# AccBottom.net
KiCad netlist of a schematic drawn in Altium Designer
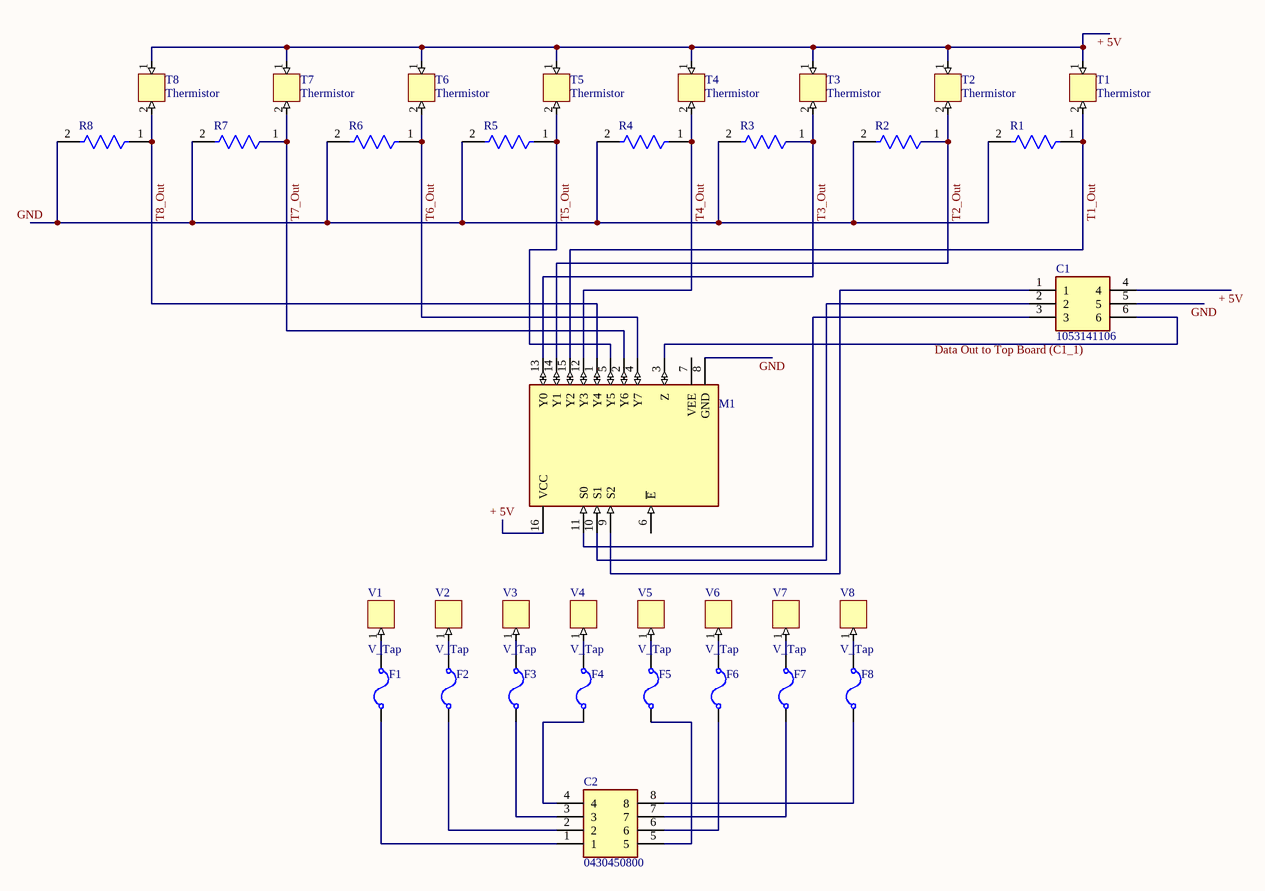
[diagram p0: AccBottom.SchDoc]

(export (version "E")
  (design (tool "Eeschema 10.0.6"))
  (components
    (comp (ref "C1")
      (value "1053141106")
      (footprint "6 Pin Dual Nano")
      (libsource (lib "AccBottom") (part "1053141106"))
    )
    (comp (ref "C2")
      (value "0430450800")
      (footprint "8 Pin Dual")
      (description "Micro-Fit (3.0) dual row, right angle, thru hole header")
      (libsource (lib "AccBottom") (part "0430450800"))
    )
    (comp (ref "F1")
      (value "0ACG-1000-TE")
      (footprint "Fuse")
      (description "Electric Fuse, 1A, 350VAC, 500VDC, 100A (IR), Surface Mount")
      (fields (field (name "MANUFACTURER") "Bel"))
      (libsource (lib "AccBottom") (part "0ACG-1000-TE"))
    )
    (comp (ref "F2")
      (value "0ACG-1000-TE")
      (footprint "Fuse")
      (description "Electric Fuse, 1A, 350VAC, 500VDC, 100A (IR), Surface Mount")
      (fields (field (name "MANUFACTURER") "Bel"))
      (libsource (lib "AccBottom") (part "0ACG-1000-TE"))
    )
    (comp (ref "F3")
      (value "0ACG-1000-TE")
      (footprint "Fuse")
      (description "Electric Fuse, 1A, 350VAC, 500VDC, 100A (IR), Surface Mount")
      (fields (field (name "MANUFACTURER") "Bel"))
      (libsource (lib "AccBottom") (part "0ACG-1000-TE"))
    )
    (comp (ref "F4")
      (value "0ACG-1000-TE")
      (footprint "Fuse")
      (description "Electric Fuse, 1A, 350VAC, 500VDC, 100A (IR), Surface Mount")
      (fields (field (name "MANUFACTURER") "Bel"))
      (libsource (lib "AccBottom") (part "0ACG-1000-TE"))
    )
    (comp (ref "F5")
      (value "0ACG-1000-TE")
      (footprint "Fuse")
      (description "Electric Fuse, 1A, 350VAC, 500VDC, 100A (IR), Surface Mount")
      (fields (field (name "MANUFACTURER") "Bel"))
      (libsource (lib "AccBottom") (part "0ACG-1000-TE"))
    )
    (comp (ref "F6")
      (value "0ACG-1000-TE")
      (footprint "Fuse")
      (description "Electric Fuse, 1A, 350VAC, 500VDC, 100A (IR), Surface Mount")
      (fields (field (name "MANUFACTURER") "Bel"))
      (libsource (lib "AccBottom") (part "0ACG-1000-TE"))
    )
    (comp (ref "F7")
      (value "0ACG-1000-TE")
      (footprint "Fuse")
      (description "Electric Fuse, 1A, 350VAC, 500VDC, 100A (IR), Surface Mount")
      (fields (field (name "MANUFACTURER") "Bel"))
      (libsource (lib "AccBottom") (part "0ACG-1000-TE"))
    )
    (comp (ref "F8")
      (value "0ACG-1000-TE")
      (footprint "Fuse")
      (description "Electric Fuse, 1A, 350VAC, 500VDC, 100A (IR), Surface Mount")
      (fields (field (name "MANUFACTURER") "Bel"))
      (libsource (lib "AccBottom") (part "0ACG-1000-TE"))
    )
    (comp (ref "M1")
      (value "74HC4051D,653")
      (footprint "8x1MUX")
      (description "IC MUX/DEMUX 8X1 16SOIC")
      (libsource (lib "AccBottom") (part "74HC4051D"))
    )
    (comp (ref "R1")
      (value "RC0805FR-133K3L")
      (footprint "3.3kRes")
      (fields
        (field (name "TOLERANCE") "1%")
        (field (name "MANUFACTURER") "KOA Speer")
        (field (name "MANUFACTURER PART NUMBER") "RK73G2ATTD3301F")
      )
      (libsource (lib "AccBottom") (part "RC0805FR-133K3L"))
    )
    (comp (ref "R2")
      (value "RC0805FR-133K3L")
      (footprint "3.3kRes")
      (fields
        (field (name "TOLERANCE") "1%")
        (field (name "MANUFACTURER") "KOA Speer")
        (field (name "MANUFACTURER PART NUMBER") "RK73G2ATTD3301F")
      )
      (libsource (lib "AccBottom") (part "RC0805FR-133K3L"))
    )
    (comp (ref "R3")
      (value "RC0805FR-133K3L")
      (footprint "3.3kRes")
      (fields
        (field (name "TOLERANCE") "1%")
        (field (name "MANUFACTURER") "KOA Speer")
        (field (name "MANUFACTURER PART NUMBER") "RK73G2ATTD3301F")
      )
      (libsource (lib "AccBottom") (part "RC0805FR-133K3L"))
    )
    (comp (ref "R4")
      (value "RC0805FR-133K3L")
      (footprint "3.3kRes")
      (fields
        (field (name "TOLERANCE") "1%")
        (field (name "MANUFACTURER") "KOA Speer")
        (field (name "MANUFACTURER PART NUMBER") "RK73G2ATTD3301F")
      )
      (libsource (lib "AccBottom") (part "RC0805FR-133K3L"))
    )
    (comp (ref "R5")
      (value "RC0805FR-133K3L")
      (footprint "3.3kRes")
      (fields
        (field (name "TOLERANCE") "1%")
        (field (name "MANUFACTURER") "KOA Speer")
        (field (name "MANUFACTURER PART NUMBER") "RK73G2ATTD3301F")
      )
      (libsource (lib "AccBottom") (part "RC0805FR-133K3L"))
    )
    (comp (ref "R6")
      (value "RC0805FR-133K3L")
      (footprint "3.3kRes")
      (fields
        (field (name "TOLERANCE") "1%")
        (field (name "MANUFACTURER") "KOA Speer")
        (field (name "MANUFACTURER PART NUMBER") "RK73G2ATTD3301F")
      )
      (libsource (lib "AccBottom") (part "RC0805FR-133K3L"))
    )
    (comp (ref "R7")
      (value "RC0805FR-133K3L")
      (footprint "3.3kRes")
      (fields
        (field (name "TOLERANCE") "1%")
        (field (name "MANUFACTURER") "KOA Speer")
        (field (name "MANUFACTURER PART NUMBER") "RK73G2ATTD3301F")
      )
      (libsource (lib "AccBottom") (part "RC0805FR-133K3L"))
    )
    (comp (ref "R8")
      (value "RC0805FR-133K3L")
      (footprint "3.3kRes")
      (fields
        (field (name "TOLERANCE") "1%")
        (field (name "MANUFACTURER") "KOA Speer")
        (field (name "MANUFACTURER PART NUMBER") "RK73G2ATTD3301F")
      )
      (libsource (lib "AccBottom") (part "RC0805FR-133K3L"))
    )
    (comp (ref "T1")
      (value "Thermistor")
      (footprint "Thermistor")
      (libsource (lib "AccBottom") (part "Thermistor"))
    )
    (comp (ref "T2")
      (value "Thermistor")
      (footprint "Thermistor")
      (libsource (lib "AccBottom") (part "Thermistor"))
    )
    (comp (ref "T3")
      (value "Thermistor")
      (footprint "Thermistor")
      (libsource (lib "AccBottom") (part "Thermistor"))
    )
    (comp (ref "T4")
      (value "Thermistor")
      (footprint "Thermistor")
      (libsource (lib "AccBottom") (part "Thermistor"))
    )
    (comp (ref "T5")
      (value "Thermistor")
      (footprint "Thermistor")
      (libsource (lib "AccBottom") (part "Thermistor"))
    )
    (comp (ref "T6")
      (value "Thermistor")
      (footprint "Thermistor")
      (libsource (lib "AccBottom") (part "Thermistor"))
    )
    (comp (ref "T7")
      (value "Thermistor")
      (footprint "Thermistor")
      (libsource (lib "AccBottom") (part "Thermistor"))
    )
    (comp (ref "T8")
      (value "Thermistor")
      (footprint "Thermistor")
      (libsource (lib "AccBottom") (part "Thermistor"))
    )
    (comp (ref "V1") (value "V_Tap") (footprint "Voltage tap") (libsource (lib "AccBottom") (part "V_Tap")))
    (comp (ref "V2") (value "V_Tap") (footprint "Voltage tap") (libsource (lib "AccBottom") (part "V_Tap")))
    (comp (ref "V3") (value "V_Tap") (footprint "Voltage tap") (libsource (lib "AccBottom") (part "V_Tap")))
    (comp (ref "V4") (value "V_Tap") (footprint "Voltage tap") (libsource (lib "AccBottom") (part "V_Tap")))
    (comp (ref "V5") (value "V_Tap") (footprint "Voltage tap") (libsource (lib "AccBottom") (part "V_Tap")))
    (comp (ref "V6") (value "V_Tap") (footprint "Voltage tap") (libsource (lib "AccBottom") (part "V_Tap")))
    (comp (ref "V7") (value "V_Tap") (footprint "Voltage tap") (libsource (lib "AccBottom") (part "V_Tap")))
    (comp (ref "V8") (value "V_Tap") (footprint "Voltage tap") (libsource (lib "AccBottom") (part "V_Tap")))
  )
  (nets
    (net (code "1") (name "/+ 5V") (class "Default")
      (node (ref "C1") (pin "4") (pinfunction "4_4") (pintype "passive"))
      (node (ref "M1") (pin "16") (pinfunction "VCC_16") (pintype "power_in"))
      (node (ref "T1") (pin "1") (pintype "input"))
      (node (ref "T2") (pin "1") (pintype "input"))
      (node (ref "T3") (pin "1") (pintype "input"))
      (node (ref "T4") (pin "1") (pintype "input"))
      (node (ref "T5") (pin "1") (pintype "input"))
      (node (ref "T6") (pin "1") (pintype "input"))
      (node (ref "T7") (pin "1") (pintype "input"))
      (node (ref "T8") (pin "1") (pintype "input"))
    )
    (net (code "3") (name "/GND") (class "Default")
      (node (ref "C1") (pin "5") (pinfunction "5_5") (pintype "passive"))
      (node (ref "M1") (pin "8") (pinfunction "GND_8") (pintype "power_in"))
      (node (ref "R1") (pin "2") (pinfunction "2_2") (pintype "passive"))
      (node (ref "R2") (pin "2") (pinfunction "2_2") (pintype "passive"))
      (node (ref "R3") (pin "2") (pinfunction "2_2") (pintype "passive"))
      (node (ref "R4") (pin "2") (pinfunction "2_2") (pintype "passive"))
      (node (ref "R5") (pin "2") (pinfunction "2_2") (pintype "passive"))
      (node (ref "R6") (pin "2") (pinfunction "2_2") (pintype "passive"))
      (node (ref "R7") (pin "2") (pinfunction "2_2") (pintype "passive"))
      (node (ref "R8") (pin "2") (pinfunction "2_2") (pintype "passive"))
    )
    (net (code "4") (name "/T1_Out") (class "Default")
      (node (ref "M1") (pin "15") (pinfunction "Y2_15") (pintype "bidirectional"))
      (node (ref "R1") (pin "1") (pinfunction "1_1") (pintype "passive"))
      (node (ref "T1") (pin "2") (pintype "input"))
    )
    (net (code "5") (name "/T2_Out") (class "Default")
      (node (ref "M1") (pin "14") (pinfunction "Y1_14") (pintype "bidirectional"))
      (node (ref "R2") (pin "1") (pinfunction "1_1") (pintype "passive"))
      (node (ref "T2") (pin "2") (pintype "input"))
    )
    (net (code "6") (name "/T3_Out") (class "Default")
      (node (ref "M1") (pin "13") (pinfunction "Y0_13") (pintype "bidirectional"))
      (node (ref "R3") (pin "1") (pinfunction "1_1") (pintype "passive"))
      (node (ref "T3") (pin "2") (pintype "input"))
    )
    (net (code "7") (name "/T4_Out") (class "Default")
      (node (ref "M1") (pin "12") (pinfunction "Y3_12") (pintype "bidirectional"))
      (node (ref "R4") (pin "1") (pinfunction "1_1") (pintype "passive"))
      (node (ref "T4") (pin "2") (pintype "input"))
    )
    (net (code "8") (name "/T5_Out") (class "Default")
      (node (ref "M1") (pin "5") (pinfunction "Y5_5") (pintype "bidirectional"))
      (node (ref "R5") (pin "1") (pinfunction "1_1") (pintype "passive"))
      (node (ref "T5") (pin "2") (pintype "input"))
    )
    (net (code "9") (name "/T6_Out") (class "Default")
      (node (ref "M1") (pin "4") (pinfunction "Y7_4") (pintype "bidirectional"))
      (node (ref "R6") (pin "1") (pinfunction "1_1") (pintype "passive"))
      (node (ref "T6") (pin "2") (pintype "input"))
    )
    (net (code "10") (name "/T7_Out") (class "Default")
      (node (ref "M1") (pin "2") (pinfunction "Y6_2") (pintype "bidirectional"))
      (node (ref "R7") (pin "1") (pinfunction "1_1") (pintype "passive"))
      (node (ref "T7") (pin "2") (pintype "input"))
    )
    (net (code "11") (name "/T8_Out") (class "Default")
      (node (ref "M1") (pin "1") (pinfunction "Y4_1") (pintype "bidirectional"))
      (node (ref "R8") (pin "1") (pinfunction "1_1") (pintype "passive"))
      (node (ref "T8") (pin "2") (pintype "input"))
    )
    (net (code "12") (name "Net-(C2-Pad1)") (class "Default")
      (node (ref "C2") (pin "1") (pinfunction "1_1") (pintype "passive"))
      (node (ref "F1") (pin "1") (pinfunction "PB6_1") (pintype "passive"))
    )
    (net (code "13") (name "Net-(C2-Pad2)") (class "Default")
      (node (ref "C2") (pin "2") (pinfunction "2_2") (pintype "passive"))
      (node (ref "F2") (pin "1") (pinfunction "PB6_1") (pintype "passive"))
    )
    (net (code "14") (name "Net-(C2-Pad3)") (class "Default")
      (node (ref "C2") (pin "3") (pinfunction "3_3") (pintype "passive"))
      (node (ref "F3") (pin "1") (pinfunction "PB6_1") (pintype "passive"))
    )
    (net (code "15") (name "Net-(C2-Pad4)") (class "Default")
      (node (ref "C2") (pin "4") (pinfunction "4_4") (pintype "passive"))
      (node (ref "F4") (pin "1") (pinfunction "PB6_1") (pintype "passive"))
    )
    (net (code "16") (name "Net-(C2-Pad5)") (class "Default")
      (node (ref "C2") (pin "5") (pinfunction "5_5") (pintype "passive"))
      (node (ref "F5") (pin "1") (pinfunction "PB6_1") (pintype "passive"))
    )
    (net (code "17") (name "Net-(C2-Pad6)") (class "Default")
      (node (ref "C2") (pin "6") (pinfunction "6_6") (pintype "passive"))
      (node (ref "F6") (pin "1") (pinfunction "PB6_1") (pintype "passive"))
    )
    (net (code "18") (name "Net-(C2-Pad7)") (class "Default")
      (node (ref "C2") (pin "7") (pinfunction "7_7") (pintype "passive"))
      (node (ref "F7") (pin "1") (pinfunction "PB6_1") (pintype "passive"))
    )
    (net (code "19") (name "Net-(C2-Pad8)") (class "Default")
      (node (ref "C2") (pin "8") (pinfunction "8_8") (pintype "passive"))
      (node (ref "F8") (pin "1") (pinfunction "PB6_1") (pintype "passive"))
    )
    (net (code "20") (name "Net-(F1-PB6-Pad2)") (class "Default")
      (node (ref "F1") (pin "2") (pinfunction "PB6_2") (pintype "passive"))
      (node (ref "V1") (pin "1") (pintype "input"))
    )
    (net (code "21") (name "Net-(F2-PB6-Pad2)") (class "Default")
      (node (ref "F2") (pin "2") (pinfunction "PB6_2") (pintype "passive"))
      (node (ref "V2") (pin "1") (pintype "input"))
    )
    (net (code "22") (name "Net-(F3-PB6-Pad2)") (class "Default")
      (node (ref "F3") (pin "2") (pinfunction "PB6_2") (pintype "passive"))
      (node (ref "V3") (pin "1") (pintype "input"))
    )
    (net (code "23") (name "Net-(F4-PB6-Pad2)") (class "Default")
      (node (ref "F4") (pin "2") (pinfunction "PB6_2") (pintype "passive"))
      (node (ref "V4") (pin "1") (pintype "input"))
    )
    (net (code "24") (name "Net-(F5-PB6-Pad2)") (class "Default")
      (node (ref "F5") (pin "2") (pinfunction "PB6_2") (pintype "passive"))
      (node (ref "V5") (pin "1") (pintype "input"))
    )
    (net (code "25") (name "Net-(F6-PB6-Pad2)") (class "Default")
      (node (ref "F6") (pin "2") (pinfunction "PB6_2") (pintype "passive"))
      (node (ref "V6") (pin "1") (pintype "input"))
    )
    (net (code "26") (name "Net-(F7-PB6-Pad2)") (class "Default")
      (node (ref "F7") (pin "2") (pinfunction "PB6_2") (pintype "passive"))
      (node (ref "V7") (pin "1") (pintype "input"))
    )
    (net (code "27") (name "Net-(F8-PB6-Pad2)") (class "Default")
      (node (ref "F8") (pin "2") (pinfunction "PB6_2") (pintype "passive"))
      (node (ref "V8") (pin "1") (pintype "input"))
    )
    (net (code "28") (name "Net-(M1-S0)") (class "Default")
      (node (ref "C1") (pin "3") (pinfunction "3_3") (pintype "passive"))
      (node (ref "M1") (pin "11") (pinfunction "S0_11") (pintype "input"))
    )
    (net (code "29") (name "Net-(M1-S1)") (class "Default")
      (node (ref "C1") (pin "2") (pinfunction "2_2") (pintype "passive"))
      (node (ref "M1") (pin "10") (pinfunction "S1_10") (pintype "input"))
    )
    (net (code "30") (name "Net-(M1-S2)") (class "Default")
      (node (ref "C1") (pin "1") (pinfunction "1_1") (pintype "passive"))
      (node (ref "M1") (pin "9") (pinfunction "S2_9") (pintype "input"))
    )
    (net (code "31") (name "Net-(M1-Z)") (class "Default")
      (node (ref "C1") (pin "6") (pinfunction "6_6") (pintype "passive"))
      (node (ref "M1") (pin "3") (pinfunction "Z_3") (pintype "bidirectional"))
    )
    (net (code "32") (name "unconnected-(M1-VEE-Pad7)") (class "Default")
      (node (ref "M1") (pin "7") (pinfunction "VEE_7") (pintype "power_in"))
    )
    (net (code "33") (name "unconnected-(M1-~{E}-Pad6)") (class "Default")
      (node (ref "M1") (pin "6") (pinfunction "~{E}_6") (pintype "input"))
    )
  )
)
